# BaseCircuit.net
KiCad netlist of a schematic drawn in Altium Designer
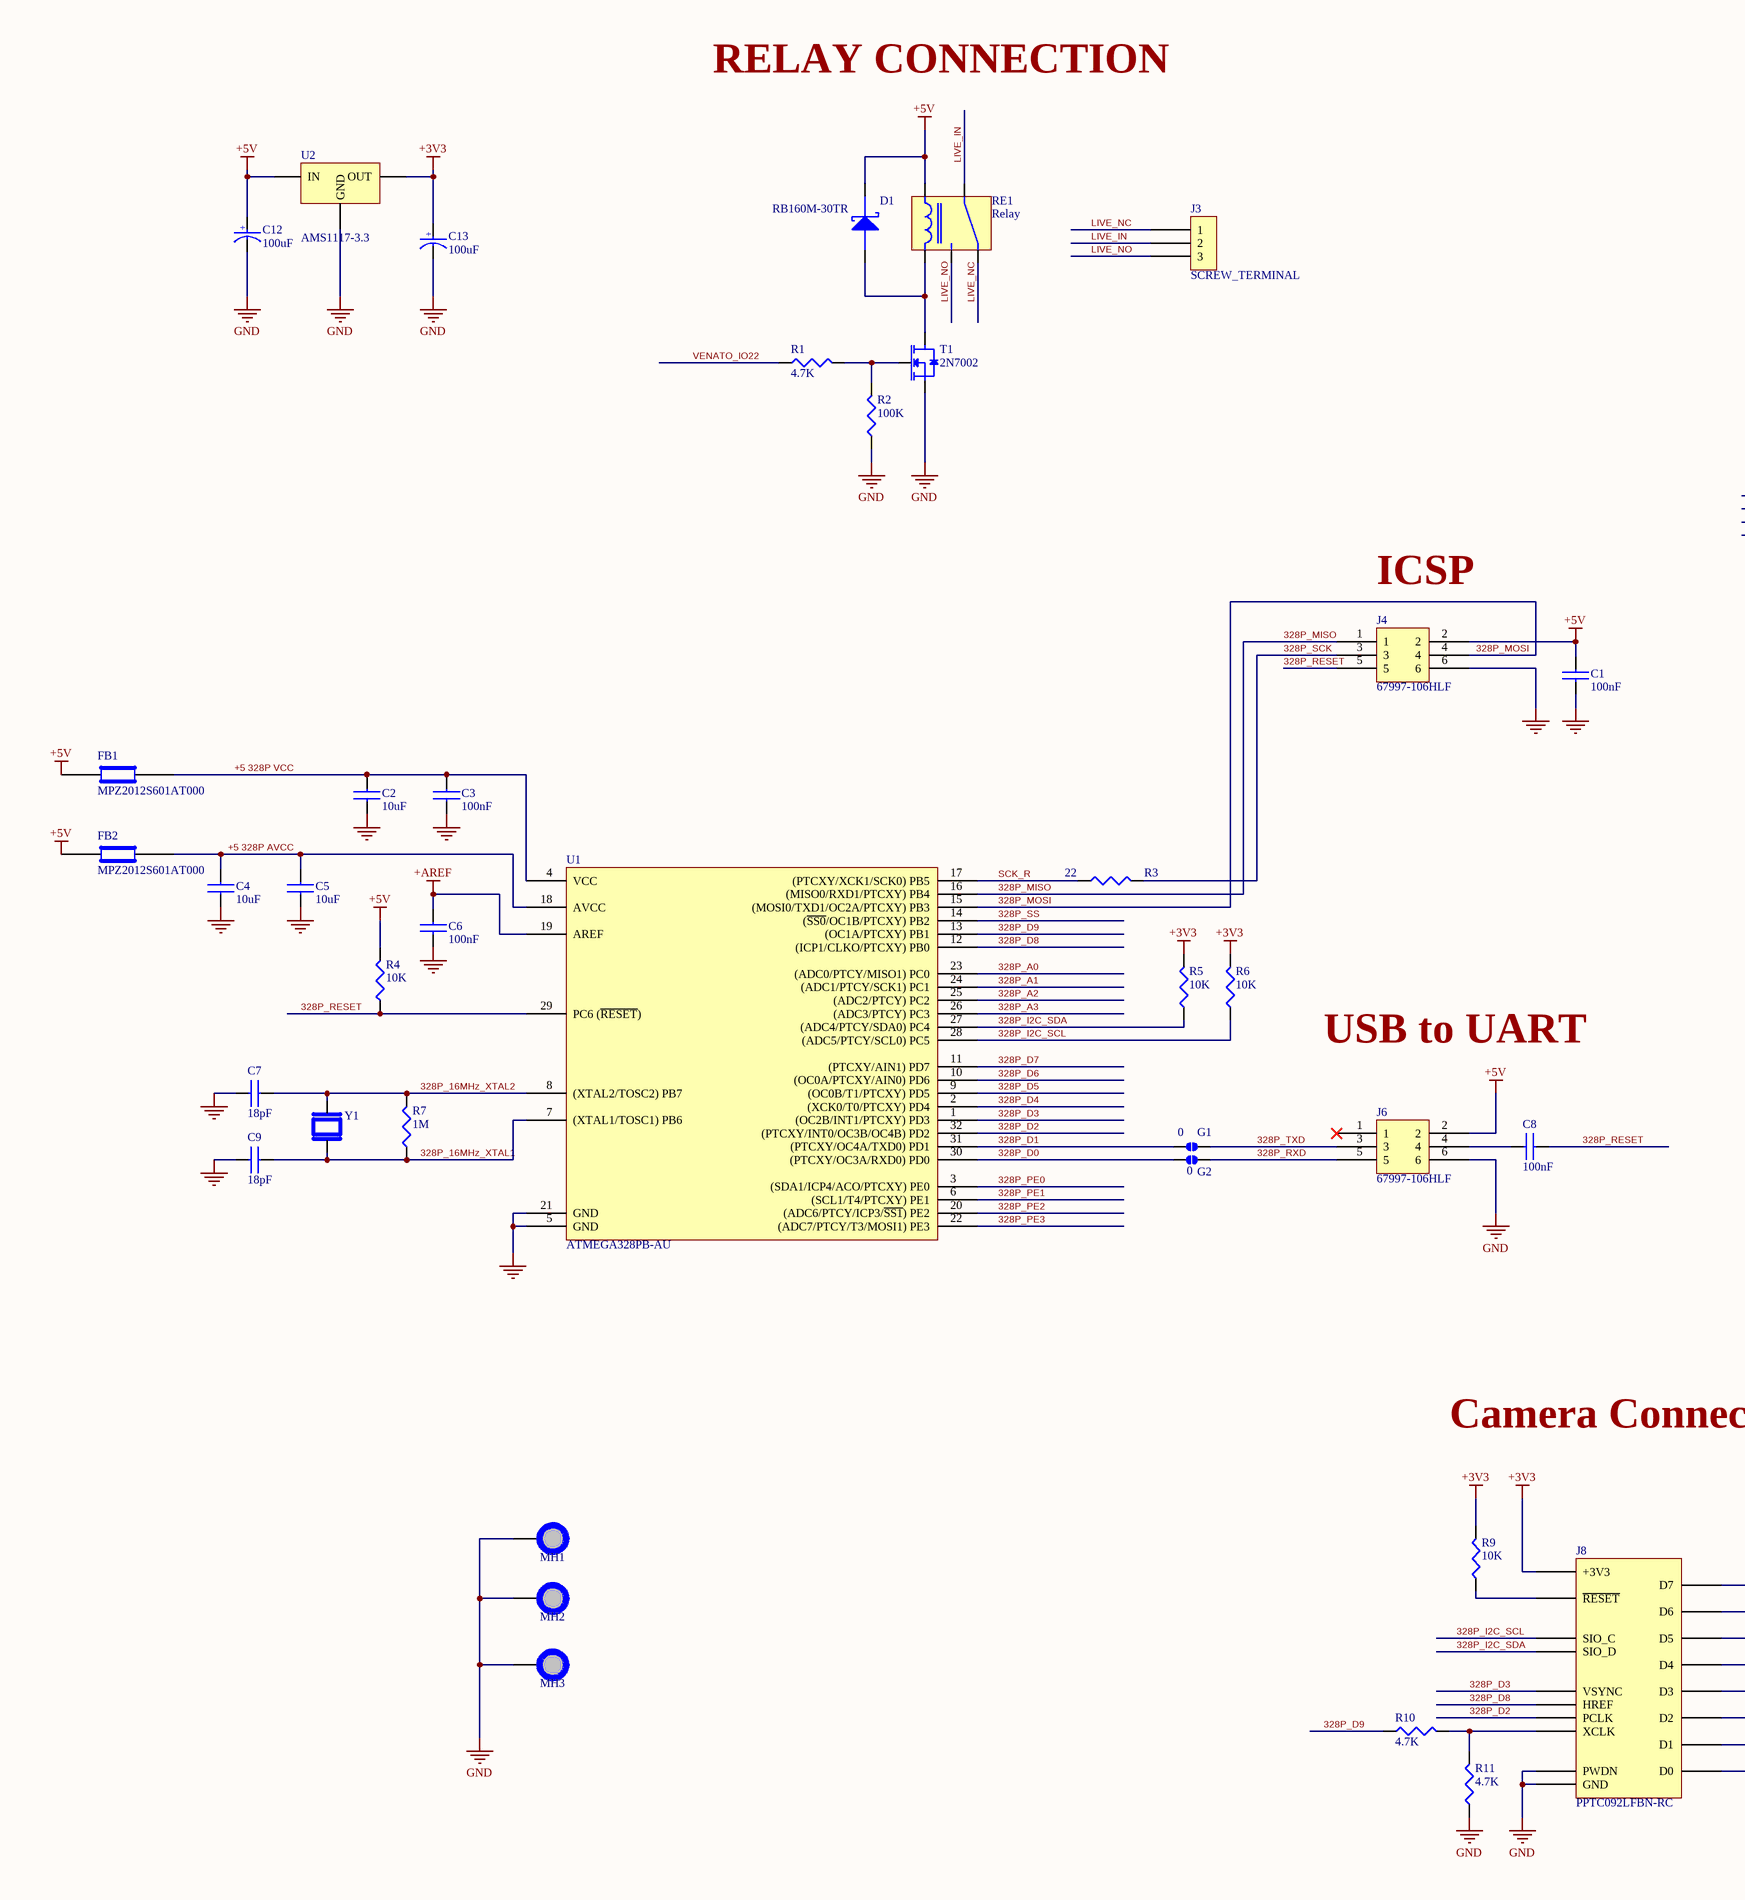
[diagram p0: BaseCircuit.SchDoc, left]
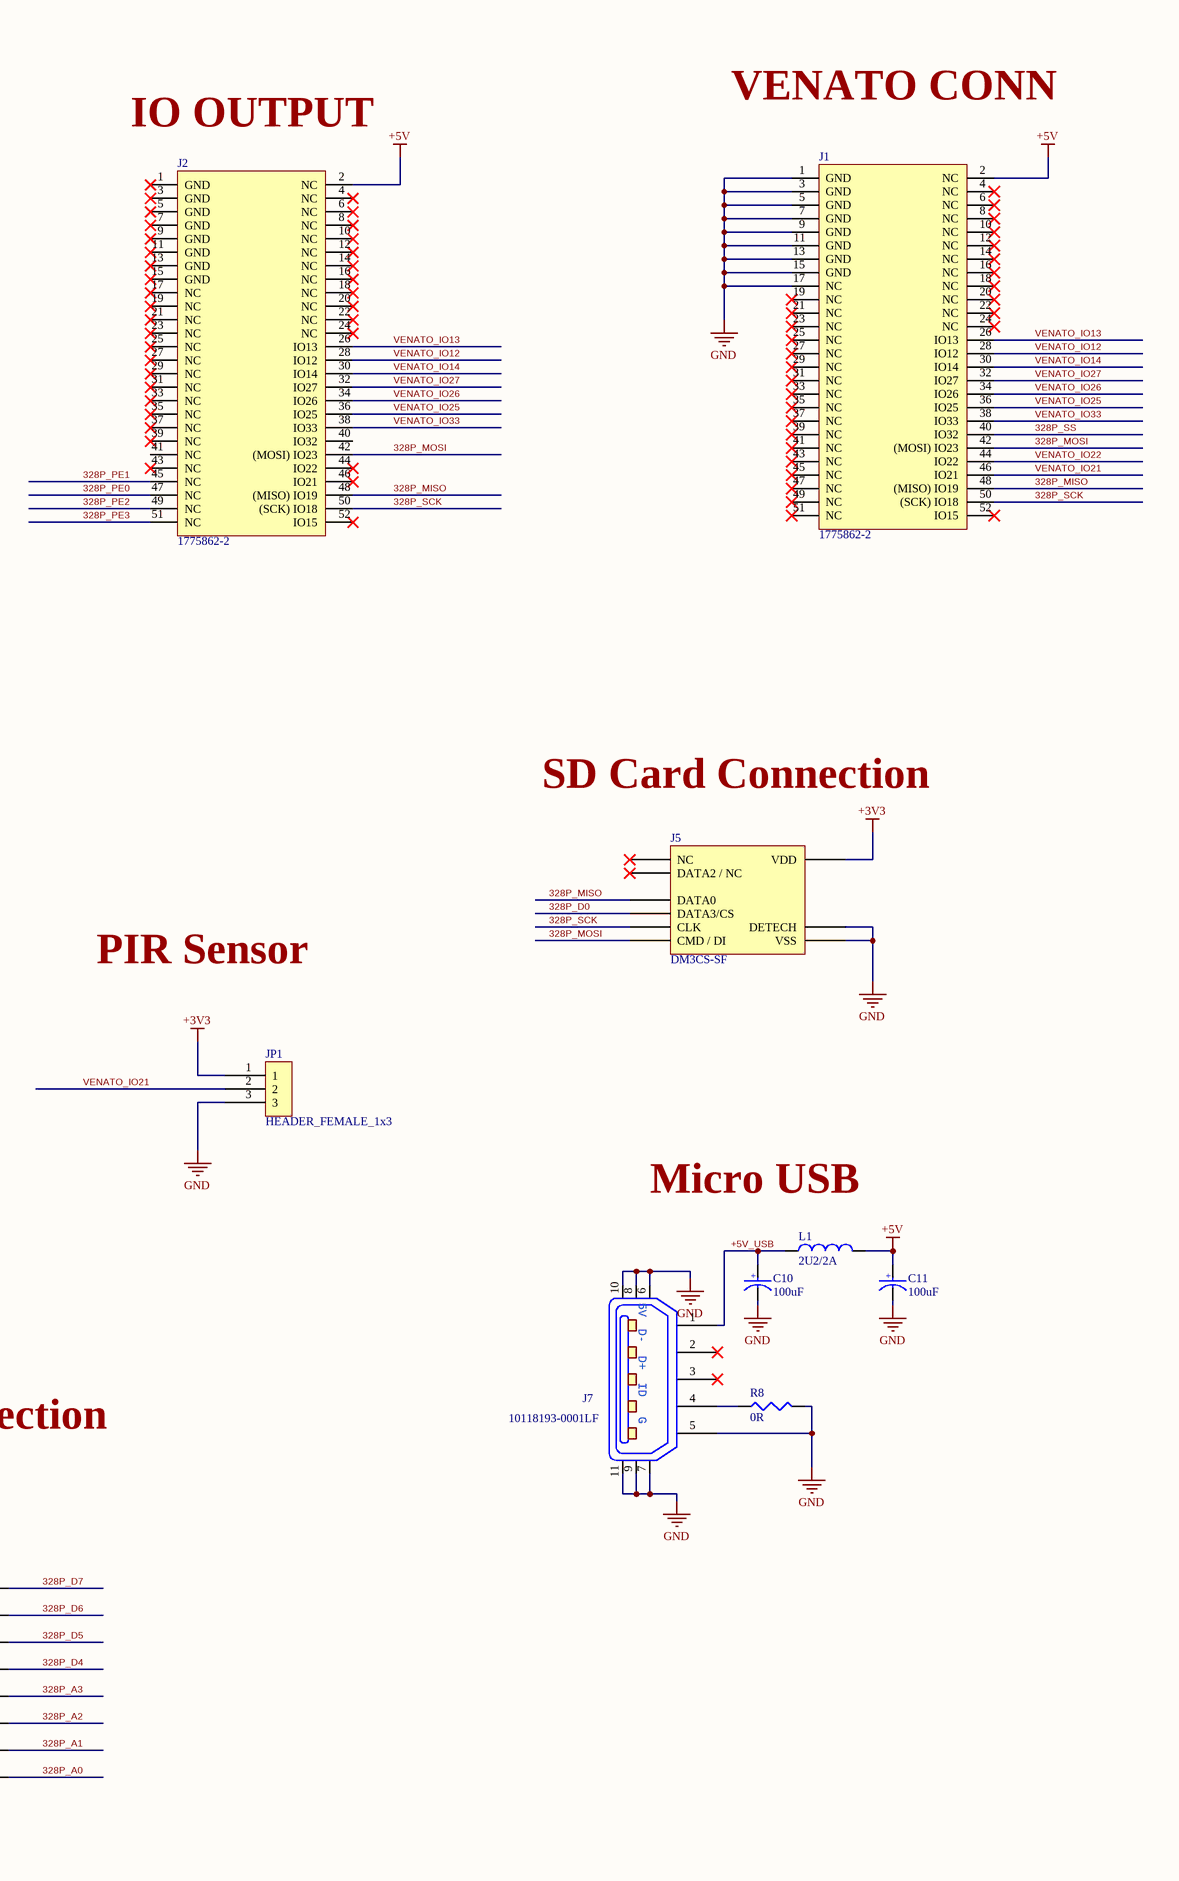
[diagram p1: BaseCircuit.SchDoc, right]

(export (version "E")
  (design (tool "Eeschema 10.0.6"))
  (components
    (comp (ref "C1")
      (value "100nF")
      (footprint "C0805")
      (description "Cap Ceramic 0.1uF 50V X7R 10% Pad SMD 0805 125°C Automotive T/R")
      (fields
        (field (name "MANUFACTURER") "TDK")
        (field (name "MANUFACTURER PART NUMBER") "CGA4J2X7R1H104K125AM")
      )
      (libsource (lib "atmega_shlib") (part "CGA4J2X7R1H104K125AM"))
    )
    (comp (ref "C2")
      (value "10uF")
      (footprint "C0805")
      (description "Cap Ceramic 10uF 10V X7S 20% Pad SMD 0805 125°C Low ESR Automotive T/R")
      (fields
        (field (name "MANUFACTURER") "TDK")
        (field (name "MANUFACTURER PART NUMBER") "CGA4J3X7S1A106M125AB")
      )
      (libsource (lib "atmega_shlib") (part "CGA4J3X7S1A106M125AB"))
    )
    (comp (ref "C3")
      (value "100nF")
      (footprint "C0805")
      (description "Cap Ceramic 0.1uF 50V X7R 10% Pad SMD 0805 125°C Automotive T/R")
      (fields
        (field (name "MANUFACTURER") "TDK")
        (field (name "MANUFACTURER PART NUMBER") "CGA4J2X7R1H104K125AM")
      )
      (libsource (lib "atmega_shlib") (part "CGA4J2X7R1H104K125AM"))
    )
    (comp (ref "C4")
      (value "10uF")
      (footprint "C0805")
      (description "Cap Ceramic 10uF 10V X7S 20% Pad SMD 0805 125°C Low ESR Automotive T/R")
      (fields
        (field (name "MANUFACTURER") "TDK")
        (field (name "MANUFACTURER PART NUMBER") "CGA4J3X7S1A106M125AB")
      )
      (libsource (lib "atmega_shlib") (part "CGA4J3X7S1A106M125AB"))
    )
    (comp (ref "C5")
      (value "10uF")
      (footprint "C0805")
      (description "Cap Ceramic 10uF 10V X7S 20% Pad SMD 0805 125°C Low ESR Automotive T/R")
      (fields
        (field (name "MANUFACTURER") "TDK")
        (field (name "MANUFACTURER PART NUMBER") "CGA4J3X7S1A106M125AB")
      )
      (libsource (lib "atmega_shlib") (part "CGA4J3X7S1A106M125AB"))
    )
    (comp (ref "C6")
      (value "100nF")
      (footprint "C0805")
      (description "Cap Ceramic 0.1uF 50V X7R 10% Pad SMD 0805 125°C Automotive T/R")
      (fields
        (field (name "MANUFACTURER") "TDK")
        (field (name "MANUFACTURER PART NUMBER") "CGA4J2X7R1H104K125AM")
      )
      (libsource (lib "atmega_shlib") (part "CGA4J2X7R1H104K125AM"))
    )
    (comp (ref "C7")
      (value "18pF")
      (footprint "C0805")
      (description "Cap Ceramic 18pF 50V C0G 5% SMD 0805 125C Paper T/R")
      (fields
        (field (name "MANUFACTURER") "KEMET")
        (field (name "MANUFACTURER PART NUMBER") "C0805C180J5GACTU")
      )
      (libsource (lib "atmega_shlib") (part "C0805C180J5GACTU"))
    )
    (comp (ref "C8")
      (value "100nF")
      (footprint "C0805")
      (description "Cap Ceramic 0.1uF 50V X7R 10% Pad SMD 0805 125°C Automotive T/R")
      (fields
        (field (name "MANUFACTURER") "TDK")
        (field (name "MANUFACTURER PART NUMBER") "CGA4J2X7R1H104K125AM")
      )
      (libsource (lib "atmega_shlib") (part "CGA4J2X7R1H104K125AM"))
    )
    (comp (ref "C9")
      (value "18pF")
      (footprint "C0805")
      (description "Cap Ceramic 18pF 50V C0G 5% SMD 0805 125C Paper T/R")
      (fields
        (field (name "MANUFACTURER") "KEMET")
        (field (name "MANUFACTURER PART NUMBER") "C0805C180J5GACTU")
      )
      (libsource (lib "atmega_shlib") (part "C0805C180J5GACTU"))
    )
    (comp (ref "C10")
      (value "100uF")
      (footprint "C_ALU_C_SIZE")
      (description "Cap Aluminum 100uF 10V 20% (5 X 5.4mm) SMD 50mA 1000 hr 85°C T/R")
      (fields
        (field (name "MANUFACTURER") "Panasonic")
        (field (name "MANUFACTURER PART NUMBER") "EEE-1AA101WR")
      )
      (libsource (lib "schmaticSMDv1") (part "EEE-1AA101WR"))
    )
    (comp (ref "C11")
      (value "100uF")
      (footprint "C_ALU_C_SIZE")
      (description "Cap Aluminum 100uF 10V 20% (5 X 5.4mm) SMD 50mA 1000 hr 85°C T/R")
      (fields
        (field (name "MANUFACTURER") "Panasonic")
        (field (name "MANUFACTURER PART NUMBER") "EEE-1AA101WR")
      )
      (libsource (lib "schmaticSMDv1") (part "EEE-1AA101WR"))
    )
    (comp (ref "C12")
      (value "100uF")
      (footprint "C_ALU_C_SIZE")
      (description "Cap Aluminum 100uF 10V 20% (5 X 5.4mm) SMD 50mA 1000 hr 85°C T/R")
      (fields
        (field (name "MANUFACTURER") "Panasonic")
        (field (name "MANUFACTURER PART NUMBER") "EEE-1AA101WR")
      )
      (libsource (lib "schmaticSMDv1") (part "EEE-1AA101WR"))
    )
    (comp (ref "C13")
      (value "100uF")
      (footprint "C_ALU_C_SIZE")
      (description "Cap Aluminum 100uF 10V 20% (5 X 5.4mm) SMD 50mA 1000 hr 85°C T/R")
      (fields
        (field (name "MANUFACTURER") "Panasonic")
        (field (name "MANUFACTURER PART NUMBER") "EEE-1AA101WR")
      )
      (libsource (lib "schmaticSMDv1") (part "EEE-1AA101WR"))
    )
    (comp (ref "D1")
      (value "RB160M-30TR")
      (footprint "SOD123")
      (description "DIODE SCHOTTKY 30V 1A PMDU")
      (fields (field (name "MANUFACTURER") "Rohm"))
      (libsource (lib "schmaticSMDv1") (part "RB160M-30TR"))
    )
    (comp (ref "FB1")
      (value "MPZ2012S601AT000")
      (footprint "C0805")
      (description "Ferrite Beads Multi-Layer Power 600Ohm 25% 100MHz 2A 100mOhm DCR 0805 T/R")
      (fields (field (name "MANUFACTURER") "TDK"))
      (libsource (lib "atmega_shlib") (part "MPZ2012S601AT000"))
    )
    (comp (ref "FB2")
      (value "MPZ2012S601AT000")
      (footprint "C0805")
      (description "Ferrite Beads Multi-Layer Power 600Ohm 25% 100MHz 2A 100mOhm DCR 0805 T/R")
      (fields (field (name "MANUFACTURER") "TDK"))
      (libsource (lib "atmega_shlib") (part "MPZ2012S601AT000"))
    )
    (comp (ref "G1")
      (value "0")
      (footprint "R0805_no_3d")
      (description "This is a gap that diconects line. you can connect it using soldier")
      (libsource (lib "schmaticSMDv1") (part "0Ohm gap"))
    )
    (comp (ref "G2")
      (value "0")
      (footprint "R0805_no_3d")
      (description "This is a gap that diconects line. you can connect it using soldier")
      (libsource (lib "schmaticSMDv1") (part "0Ohm gap"))
    )
    (comp (ref "J1")
      (value "1775862-2")
      (footprint "TE_1775862-2")
      (description "MSATA/MINI PCI-E 5.2H TYPE I G/F")
      (fields (field (name "MANUFACTURER") "TE Connectivity"))
      (libsource (lib "schmaticSMDv1") (part "1775862-2"))
    )
    (comp (ref "J2")
      (value "1775862-2")
      (footprint "TE_1775862-2")
      (description "MSATA/MINI PCI-E 5.2H TYPE I G/F")
      (fields (field (name "MANUFACTURER") "TE Connectivity"))
      (libsource (lib "schmaticSMDv1") (part "1775862-2"))
    )
    (comp (ref "J3")
      (value "SCREW_TERMINAL")
      (footprint "SCREW_TERMINAL_3_5.08MM")
      (libsource (lib "schmaticSMDv1") (part "SCREW_TERMINAL"))
    )
    (comp (ref "J4")
      (value "67997-106HLF")
      (footprint "HDR_2x3_2.54MM")
      (description "Conn Unshrouded Header HDR 6 POS 2.54mm Solder ST Top Entry Thru-Hole BergStik® Bulk")
      (fields (field (name "MANUFACTURER") "ICC"))
      (libsource (lib "atmega_shlib") (part "67997-106HLF"))
    )
    (comp (ref "J5")
      (value "DM3CS-SF")
      (footprint "GCT_MEM2051-00-195-00-A")
      (description "Connector, Memory, Micro Sd, Hinged Rohs Compliant: Yes")
      (fields (field (name "MANUFACTURER") "Hirose"))
      (libsource (lib "schmaticSMDv1") (part "DM3CS-SF"))
    )
    (comp (ref "J6")
      (value "67997-106HLF")
      (footprint "HDR_2x3_2.54MM")
      (description "Conn Unshrouded Header HDR 6 POS 2.54mm Solder ST Top Entry Thru-Hole BergStik® Bulk")
      (fields (field (name "MANUFACTURER") "ICC"))
      (libsource (lib "atmega_shlib") (part "67997-106HLF"))
    )
    (comp (ref "J7")
      (value "10118193-0001LF")
      (footprint "10118193-0001LF")
      (description "FCI Right Angle Surface Mount Mount Female USB Connector; 100 V ac; 1.8A")
      (fields (field (name "MANUFACTURER") "Amphenol ICC / FCI"))
      (libsource (lib "atmega_shlib") (part "10118193-0001LF"))
    )
    (comp (ref "J8")
      (value "PPTC092LFBN-RC")
      (footprint "HDR_2X9_2.54MM")
      (description "Connector Header 18 Position 0.100\" (2.54mm) Tin Through Hole")
      (fields (field (name "MANUFACTURER") "Sullins"))
      (libsource (lib "schmaticSMDv1") (part "PPTC092LFBN-RC"))
    )
    (comp (ref "JP1")
      (value "HEADER_FEMALE_1x3")
      (footprint "HDR_1x3_2.54MM")
      (description "Conn Unshrouded Header HDR 3 POS 2.54mm Solder ST Top Entry Thru-Hole BergStik® Automotive Bulk")
      (fields
        (field (name "MANUFACTURER") "Amphenol ICC")
        (field (name "MANUFACTURER PART NUMBER") "68000-103HLF")
      )
      (libsource (lib "atmega_shlib") (part "68000-103HLF"))
    )
    (comp (ref "L1")
      (value "2U2/2A")
      (footprint "CL_inductor")
      (description "Inductor RF Chip Wirewound 2.2uH 20% 100KHz 1.13A 0.104Ohm DCR 1210 T/R")
      (fields
        (field (name "MANUFACTURER") "KEMET")
        (field (name "MANUFACTURER PART NUMBER") "L1210R2R2MDWIT")
      )
      (libsource (lib "atmega_shlib") (part "L1210R2R2MDWIT"))
    )
    (comp (ref "MH1")
      (value "Mounting_hole_17.4_3.2")
      (footprint "MH_17.4_3.2")
      (description "Mounting Hole plated")
      (libsource (lib "schmaticSMDv1") (part "Mounting_hole_17.4_3.2"))
    )
    (comp (ref "MH2")
      (value "Mounting_hole_17.4_3.2")
      (footprint "MH_17.4_3.2")
      (description "Mounting Hole plated")
      (libsource (lib "schmaticSMDv1") (part "Mounting_hole_17.4_3.2"))
    )
    (comp (ref "MH3")
      (value "Mounting_hole_17.4_3.2")
      (footprint "MH_17.4_3.2")
      (description "Mounting Hole plated")
      (libsource (lib "schmaticSMDv1") (part "Mounting_hole_17.4_3.2"))
    )
    (comp (ref "R1")
      (value "4.7K")
      (footprint "R0805")
      (description "Res Thick Film 0805 4.7K Ohm 5% 0.125W(1/8W) ±100ppm/C Pad SMD T/R")
      (fields
        (field (name "MANUFACTURER") "Yageo")
        (field (name "MANUFACTURER PART NUMBER") "RC0805JR-074K7L")
      )
      (libsource (lib "schmaticSMDv1") (part "RC0805JR-074K7L"))
    )
    (comp (ref "R2")
      (value "100K")
      (footprint "R0805")
      (description "Res Thick Film 0805 100K Ohm 1% 1/8W ±100ppm/°C Molded SMD Paper T/R")
      (fields
        (field (name "MANUFACTURER") "Yageo")
        (field (name "MANUFACTURER PART NUMBER") "RC0805FR-07100KL")
      )
      (libsource (lib "schmaticSMDv1") (part "RC0805FR-07100KL"))
    )
    (comp (ref "R3")
      (value "22")
      (footprint "R0805")
      (description "Res SMD 0805 22R 1% 0.125W T.C.100PPM")
      (fields
        (field (name "MANUFACTURER") "Yageo")
        (field (name "MANUFACTURER PART NUMBER") "RC0805FR-0722RL")
      )
      (libsource (lib "atmega_shlib") (part "RC0805FR-0722RL"))
    )
    (comp (ref "R4")
      (value "10K")
      (footprint "R0805")
      (description "Res SMD 0805 10K 1% 0.125W T.C.100PPM")
      (fields
        (field (name "MANUFACTURER") "Yageo")
        (field (name "MANUFACTURER PART NUMBER") "RC0805FR-0710KL")
      )
      (libsource (lib "atmega_shlib") (part "RC0805FR-0710KL"))
    )
    (comp (ref "R5")
      (value "10K")
      (footprint "R0805")
      (description "Res SMD 0805 10K 1% 0.125W T.C.100PPM")
      (fields
        (field (name "MANUFACTURER") "Yageo")
        (field (name "MANUFACTURER PART NUMBER") "RC0805FR-0710KL")
      )
      (libsource (lib "schmaticSMDv1") (part "RC0805FR-0710KL"))
    )
    (comp (ref "R6")
      (value "10K")
      (footprint "R0805")
      (description "Res SMD 0805 10K 1% 0.125W T.C.100PPM")
      (fields
        (field (name "MANUFACTURER") "Yageo")
        (field (name "MANUFACTURER PART NUMBER") "RC0805FR-0710KL")
      )
      (libsource (lib "schmaticSMDv1") (part "RC0805FR-0710KL"))
    )
    (comp (ref "R7")
      (value "1M")
      (footprint "R0805")
      (description "Res Thick Film 0805 1M Ohm 1% 0.125W(1/8W) ±100ppm/C Pad SMD T/R")
      (fields
        (field (name "MANUFACTURER") "Yageo Phycomp")
        (field (name "MANUFACTURER PART NUMBER") "RC0805FR-071ML")
      )
      (libsource (lib "atmega_shlib") (part "RC0805FR-071ML"))
    )
    (comp (ref "R8")
      (value "0R")
      (footprint "R0805")
      (description "RC Series 0805 0.125 W 0 Ohm Jumper Surface Mount Thick Film Chip Resistor")
      (fields
        (field (name "MANUFACTURER") "Yageo")
        (field (name "MANUFACTURER PART NUMBER") "RC0805JR-070RL")
      )
      (libsource (lib "atmega_shlib") (part "RC0805JR-070RL"))
    )
    (comp (ref "R9")
      (value "10K")
      (footprint "R0805")
      (description "Res SMD 0805 10K 1% 0.125W T.C.100PPM")
      (fields
        (field (name "MANUFACTURER") "Yageo")
        (field (name "MANUFACTURER PART NUMBER") "RC0805FR-0710KL")
      )
      (libsource (lib "atmega_shlib") (part "RC0805FR-0710KL"))
    )
    (comp (ref "R10")
      (value "4.7K")
      (footprint "R0805")
      (description "Res Thick Film 0805 4.7K Ohm 5% 0.125W(1/8W) ±100ppm/C Pad SMD T/R")
      (fields
        (field (name "MANUFACTURER") "Yageo")
        (field (name "MANUFACTURER PART NUMBER") "RC0805JR-074K7L")
      )
      (libsource (lib "schmaticSMDv1") (part "RC0805JR-074K7L"))
    )
    (comp (ref "R11")
      (value "4.7K")
      (footprint "R0805")
      (description "Res Thick Film 0805 4.7K Ohm 5% 0.125W(1/8W) ±100ppm/C Pad SMD T/R")
      (fields
        (field (name "MANUFACTURER") "Yageo")
        (field (name "MANUFACTURER PART NUMBER") "RC0805JR-074K7L")
      )
      (libsource (lib "schmaticSMDv1") (part "RC0805JR-074K7L"))
    )
    (comp (ref "RE1")
      (value "Relay")
      (footprint "RELAY_5PIN")
      (libsource (lib "schmaticSMDv1") (part "Relay"))
    )
    (comp (ref "T1")
      (value "2N7002")
      (footprint "TRANS_MMBT2907A")
      (description "Transistor Mosfet N-ch 60V 0.3A 3-PIN SOT-23 T/r")
      (libsource (lib "schmaticSMDv1") (part "2N7002"))
    )
    (comp (ref "U1")
      (value "ATMEGA328PB-AU")
      (footprint "TQFP_32")
      (description "IC MCU 8BIT 32KB FLASH 32TQFP")
      (fields (field (name "MANUFACTURER") "Microchip"))
      (libsource (lib "schmaticSMDv1") (part "ATMEGA328PB-AU"))
    )
    (comp (ref "U2")
      (value "AMS1117-3.3")
      (footprint "SOT-223")
      (description "Fixed Positive LDO Regulator, 3.3V, 1.3V Dropout, PDSO3")
      (fields (field (name "MANUFACTURER") "Advanced Monolithic Systems"))
      (libsource (lib "schmaticSMDv1") (part "AMS1117-3.3"))
    )
    (comp (ref "Y1")
      (value "ABLS-16.000MHZ-B4-T")
      (footprint "XTAL_ABLS-16.000MHZ-B4-T")
      (description "Crystal 16MHz ±30ppm (Tol) ±50ppm (Stability) 18pF FUND 40Ohm 2-Pin HC-49/US SMD T/R")
      (fields (field (name "MANUFACTURER") "Abracon") (field (name "TOLERANCE") "30ppm"))
      (libsource (lib "schmaticSMDv1") (part "ABLS-16.000MHZ-B4-T"))
    )
  )
  (nets
    (net (code "1") (name "+3V3") (class "Default")
      (node (ref "C13") (pin "1") (pinfunction "1_1") (pintype "passive"))
      (node (ref "J5") (pin "4") (pinfunction "VDD_4") (pintype "passive"))
      (node (ref "J8") (pin "1") (pinfunction "+3V3_1") (pintype "passive"))
      (node (ref "JP1") (pin "1") (pinfunction "1_1") (pintype "passive"))
      (node (ref "R5") (pin "2") (pinfunction "2_2") (pintype "passive"))
      (node (ref "R6") (pin "2") (pinfunction "2_2") (pintype "passive"))
      (node (ref "R9") (pin "2") (pinfunction "2_2") (pintype "passive"))
      (node (ref "U2") (pin "2") (pinfunction "OUT_2") (pintype "passive"))
    )
    (net (code "2") (name "+5V") (class "Default")
      (node (ref "C1") (pin "2") (pinfunction "2_2") (pintype "passive"))
      (node (ref "C11") (pin "1") (pinfunction "1_1") (pintype "passive"))
      (node (ref "C12") (pin "1") (pinfunction "1_1") (pintype "passive"))
      (node (ref "D1") (pin "1") (pinfunction "Ca_1") (pintype "passive"))
      (node (ref "FB1") (pin "1") (pinfunction "1_1") (pintype "passive"))
      (node (ref "FB2") (pin "1") (pinfunction "1_1") (pintype "passive"))
      (node (ref "J1") (pin "2") (pinfunction "NC_2") (pintype "passive"))
      (node (ref "J2") (pin "2") (pinfunction "NC_2") (pintype "passive"))
      (node (ref "J4") (pin "2") (pinfunction "2_2") (pintype "passive"))
      (node (ref "J6") (pin "2") (pinfunction "2_2") (pintype "passive"))
      (node (ref "L1") (pin "2") (pinfunction "2_2") (pintype "passive"))
      (node (ref "R4") (pin "2") (pinfunction "2_2") (pintype "passive"))
      (node (ref "RE1") (pin "1") (pinfunction "1_1") (pintype "passive"))
      (node (ref "U2") (pin "3") (pinfunction "IN_3") (pintype "passive"))
    )
    (net (code "3") (name "+AREF") (class "Default")
      (node (ref "C6") (pin "2") (pinfunction "2_2") (pintype "passive"))
      (node (ref "U1") (pin "19") (pinfunction "AREF_19") (pintype "passive"))
    )
    (net (code "4") (name "/+5 328P AVCC") (class "Default")
      (node (ref "C4") (pin "2") (pinfunction "2_2") (pintype "passive"))
      (node (ref "C5") (pin "2") (pinfunction "2_2") (pintype "passive"))
      (node (ref "FB2") (pin "2") (pinfunction "2_2") (pintype "passive"))
      (node (ref "U1") (pin "18") (pinfunction "AVCC_18") (pintype "passive"))
    )
    (net (code "5") (name "/+5 328P VCC") (class "Default")
      (node (ref "C2") (pin "2") (pinfunction "2_2") (pintype "passive"))
      (node (ref "C3") (pin "2") (pinfunction "2_2") (pintype "passive"))
      (node (ref "FB1") (pin "2") (pinfunction "2_2") (pintype "passive"))
      (node (ref "U1") (pin "4") (pinfunction "VCC_4") (pintype "passive"))
    )
    (net (code "6") (name "/+5V_USB") (class "Default")
      (node (ref "C10") (pin "1") (pinfunction "1_1") (pintype "passive"))
      (node (ref "J7") (pin "1") (pinfunction "1_1") (pintype "passive"))
      (node (ref "L1") (pin "1") (pinfunction "1_1") (pintype "passive"))
    )
    (net (code "7") (name "/328P_16MHz_XTAL1") (class "Default")
      (node (ref "C9") (pin "2") (pinfunction "2_2") (pintype "passive"))
      (node (ref "R7") (pin "1") (pinfunction "1_1") (pintype "passive"))
      (node (ref "U1") (pin "7") (pinfunction "(XTAL1/TOSC1)_PB6_7") (pintype "passive"))
      (node (ref "Y1") (pin "1") (pinfunction "1_1") (pintype "passive"))
    )
    (net (code "8") (name "/328P_16MHz_XTAL2") (class "Default")
      (node (ref "C7") (pin "2") (pinfunction "2_2") (pintype "passive"))
      (node (ref "R7") (pin "2") (pinfunction "2_2") (pintype "passive"))
      (node (ref "U1") (pin "8") (pinfunction "(XTAL2/TOSC2)_PB7_8") (pintype "passive"))
      (node (ref "Y1") (pin "2") (pinfunction "2_2") (pintype "passive"))
    )
    (net (code "9") (name "/328P_A0") (class "Default")
      (node (ref "J8") (pin "16") (pinfunction "D0_16") (pintype "passive"))
      (node (ref "U1") (pin "23") (pinfunction "(ADC0/PTCY/MISO1)_PC0_23") (pintype "passive"))
    )
    (net (code "10") (name "/328P_A1") (class "Default")
      (node (ref "J8") (pin "15") (pinfunction "D1_15") (pintype "passive"))
      (node (ref "U1") (pin "24") (pinfunction "(ADC1/PTCY/SCK1)_PC1_24") (pintype "passive"))
    )
    (net (code "11") (name "/328P_A2") (class "Default")
      (node (ref "J8") (pin "14") (pinfunction "D2_14") (pintype "passive"))
      (node (ref "U1") (pin "25") (pinfunction "(ADC2/PTCY)_PC2_25") (pintype "passive"))
    )
    (net (code "12") (name "/328P_A3") (class "Default")
      (node (ref "J8") (pin "13") (pinfunction "D3_13") (pintype "passive"))
      (node (ref "U1") (pin "26") (pinfunction "(ADC3/PTCY)_PC3_26") (pintype "passive"))
    )
    (net (code "13") (name "/328P_D0") (class "Default")
      (node (ref "G2") (pin "2") (pinfunction "2_2") (pintype "passive"))
      (node (ref "J5") (pin "2") (pinfunction "DATA3/CS_2") (pintype "passive"))
      (node (ref "U1") (pin "30") (pinfunction "(PTCXY/OC3A/RXD0)_PD0_30") (pintype "passive"))
    )
    (net (code "14") (name "/328P_D1") (class "Default")
      (node (ref "G1") (pin "2") (pinfunction "2_2") (pintype "passive"))
      (node (ref "U1") (pin "31") (pinfunction "(PTCXY/OC4A/TXD0)_PD1_31") (pintype "passive"))
    )
    (net (code "15") (name "/328P_D2") (class "Default")
      (node (ref "J8") (pin "7") (pinfunction "PCLK_7") (pintype "passive"))
      (node (ref "U1") (pin "32") (pinfunction "(PTCXY/INT0/OC3B/OC4B)_PD2_32") (pintype "passive"))
    )
    (net (code "16") (name "/328P_D3") (class "Default")
      (node (ref "J8") (pin "5") (pinfunction "VSYNC_5") (pintype "passive"))
      (node (ref "U1") (pin "1") (pinfunction "(OC2B/INT1/PTCXY)_PD3_1") (pintype "passive"))
    )
    (net (code "17") (name "/328P_D4") (class "Default")
      (node (ref "J8") (pin "12") (pinfunction "D4_12") (pintype "passive"))
      (node (ref "U1") (pin "2") (pinfunction "(XCK0/T0/PTCXY)_PD4_2") (pintype "passive"))
    )
    (net (code "18") (name "/328P_D5") (class "Default")
      (node (ref "J8") (pin "11") (pinfunction "D5_11") (pintype "passive"))
      (node (ref "U1") (pin "9") (pinfunction "(OC0B/T1/PTCXY)_PD5_9") (pintype "passive"))
    )
    (net (code "19") (name "/328P_D6") (class "Default")
      (node (ref "J8") (pin "10") (pinfunction "D6_10") (pintype "passive"))
      (node (ref "U1") (pin "10") (pinfunction "(OC0A/PTCXY/AIN0)_PD6_10") (pintype "passive"))
    )
    (net (code "20") (name "/328P_D7") (class "Default")
      (node (ref "J8") (pin "9") (pinfunction "D7_9") (pintype "passive"))
      (node (ref "U1") (pin "11") (pinfunction "(PTCXY/AIN1)_PD7_11") (pintype "passive"))
    )
    (net (code "21") (name "/328P_D8") (class "Default")
      (node (ref "J8") (pin "6") (pinfunction "HREF_6") (pintype "passive"))
      (node (ref "U1") (pin "12") (pinfunction "(ICP1/CLKO/PTCXY)_PB0_12") (pintype "passive"))
    )
    (net (code "22") (name "/328P_D9") (class "Default")
      (node (ref "R10") (pin "1") (pinfunction "1_1") (pintype "passive"))
      (node (ref "U1") (pin "13") (pinfunction "(OC1A/PTCXY)_PB1_13") (pintype "passive"))
    )
    (net (code "23") (name "/328P_I2C_SCL") (class "Default")
      (node (ref "J8") (pin "3") (pinfunction "SIO_C_3") (pintype "passive"))
      (node (ref "R6") (pin "1") (pinfunction "1_1") (pintype "passive"))
      (node (ref "U1") (pin "28") (pinfunction "(ADC5/PTCY/SCL0)_PC5_28") (pintype "passive"))
    )
    (net (code "24") (name "/328P_I2C_SDA") (class "Default")
      (node (ref "J8") (pin "4") (pinfunction "SIO_D_4") (pintype "passive"))
      (node (ref "R5") (pin "1") (pinfunction "1_1") (pintype "passive"))
      (node (ref "U1") (pin "27") (pinfunction "(ADC4/PTCY/SDA0)_PC4_27") (pintype "passive"))
    )
    (net (code "25") (name "/328P_MISO") (class "Default")
      (node (ref "J1") (pin "48") (pinfunction "(MISO)_IO19_48") (pintype "passive"))
      (node (ref "J2") (pin "48") (pinfunction "(MISO)_IO19_48") (pintype "passive"))
      (node (ref "J4") (pin "1") (pinfunction "1_1") (pintype "passive"))
      (node (ref "J5") (pin "7") (pinfunction "DATA0_7") (pintype "passive"))
      (node (ref "U1") (pin "16") (pinfunction "(MISO0/RXD1/PTCXY)_PB4_16") (pintype "passive"))
    )
    (net (code "26") (name "/328P_MOSI") (class "Default")
      (node (ref "J1") (pin "42") (pinfunction "(MOSI)_IO23_42") (pintype "passive"))
      (node (ref "J2") (pin "42") (pinfunction "(MOSI)_IO23_42") (pintype "passive"))
      (node (ref "J4") (pin "4") (pinfunction "4_4") (pintype "passive"))
      (node (ref "J5") (pin "3") (pinfunction "CMD_/_DI_3") (pintype "passive"))
      (node (ref "U1") (pin "15") (pinfunction "(MOSI0/TXD1/OC2A/PTCXY)_PB3_15") (pintype "passive"))
    )
    (net (code "27") (name "/328P_PE0") (class "Default")
      (node (ref "J2") (pin "47") (pinfunction "NC_47") (pintype "passive"))
      (node (ref "U1") (pin "3") (pinfunction "(SDA1/ICP4/ACO/PTCXY)_PE0_3") (pintype "passive"))
    )
    (net (code "28") (name "/328P_PE1") (class "Default")
      (node (ref "J2") (pin "45") (pinfunction "NC_45") (pintype "passive"))
      (node (ref "U1") (pin "6") (pinfunction "(SCL1/T4/PTCXY)_PE1_6") (pintype "passive"))
    )
    (net (code "29") (name "/328P_PE2") (class "Default")
      (node (ref "J2") (pin "49") (pinfunction "NC_49") (pintype "passive"))
      (node (ref "U1") (pin "20") (pinfunction "(ADC6/PTCY/ICP3/~{SS1})_PE2_20") (pintype "passive"))
    )
    (net (code "30") (name "/328P_PE3") (class "Default")
      (node (ref "J2") (pin "51") (pinfunction "NC_51") (pintype "passive"))
      (node (ref "U1") (pin "22") (pinfunction "(ADC7/PTCY/T3/MOSI1)_PE3_22") (pintype "passive"))
    )
    (net (code "31") (name "/328P_RESET") (class "Default")
      (node (ref "C8") (pin "1") (pinfunction "1_1") (pintype "passive"))
      (node (ref "J4") (pin "5") (pinfunction "5_5") (pintype "passive"))
      (node (ref "R4") (pin "1") (pinfunction "1_1") (pintype "passive"))
      (node (ref "U1") (pin "29") (pinfunction "PC6_(~{RESET})_29") (pintype "passive"))
    )
    (net (code "32") (name "/328P_RXD") (class "Default")
      (node (ref "G2") (pin "1") (pinfunction "1_1") (pintype "passive"))
      (node (ref "J6") (pin "5") (pinfunction "5_5") (pintype "passive"))
    )
    (net (code "33") (name "/328P_SCK") (class "Default")
      (node (ref "J1") (pin "50") (pinfunction "(SCK)_IO18_50") (pintype "passive"))
      (node (ref "J2") (pin "50") (pinfunction "(SCK)_IO18_50") (pintype "passive"))
      (node (ref "J4") (pin "3") (pinfunction "3_3") (pintype "passive"))
      (node (ref "J5") (pin "5") (pinfunction "CLK_5") (pintype "passive"))
      (node (ref "R3") (pin "2") (pinfunction "2_2") (pintype "passive"))
    )
    (net (code "34") (name "/328P_SS") (class "Default")
      (node (ref "J1") (pin "40") (pinfunction "IO32_40") (pintype "passive"))
      (node (ref "U1") (pin "14") (pinfunction "(~{SS0}/OC1B/PTCXY)_PB2_14") (pintype "passive"))
    )
    (net (code "35") (name "/328P_TXD") (class "Default")
      (node (ref "G1") (pin "1") (pinfunction "1_1") (pintype "passive"))
      (node (ref "J6") (pin "3") (pinfunction "3_3") (pintype "passive"))
    )
    (net (code "36") (name "/LIVE_IN") (class "Default")
      (node (ref "J3") (pin "2") (pinfunction "2_2") (pintype "passive"))
      (node (ref "RE1") (pin "5") (pinfunction "5_5") (pintype "passive"))
    )
    (net (code "37") (name "/LIVE_NC") (class "Default")
      (node (ref "J3") (pin "1") (pinfunction "1_1") (pintype "passive"))
      (node (ref "RE1") (pin "3") (pinfunction "3_3") (pintype "passive"))
    )
    (net (code "38") (name "/LIVE_NO") (class "Default")
      (node (ref "J3") (pin "3") (pinfunction "3_3") (pintype "passive"))
      (node (ref "RE1") (pin "4") (pinfunction "4_4") (pintype "passive"))
    )
    (net (code "39") (name "/SCK_R") (class "Default")
      (node (ref "R3") (pin "1") (pinfunction "1_1") (pintype "passive"))
      (node (ref "U1") (pin "17") (pinfunction "(PTCXY/XCK1/SCK0)_PB5_17") (pintype "passive"))
    )
    (net (code "40") (name "/VENATO_IO12") (class "Default")
      (node (ref "J1") (pin "28") (pinfunction "IO12_28") (pintype "passive"))
      (node (ref "J2") (pin "28") (pinfunction "IO12_28") (pintype "passive"))
    )
    (net (code "41") (name "/VENATO_IO13") (class "Default")
      (node (ref "J1") (pin "26") (pinfunction "IO13_26") (pintype "passive"))
      (node (ref "J2") (pin "26") (pinfunction "IO13_26") (pintype "passive"))
    )
    (net (code "42") (name "/VENATO_IO14") (class "Default")
      (node (ref "J1") (pin "30") (pinfunction "IO14_30") (pintype "passive"))
      (node (ref "J2") (pin "30") (pinfunction "IO14_30") (pintype "passive"))
    )
    (net (code "43") (name "/VENATO_IO21") (class "Default")
      (node (ref "J1") (pin "46") (pinfunction "IO21_46") (pintype "passive"))
      (node (ref "JP1") (pin "2") (pinfunction "2_2") (pintype "passive"))
    )
    (net (code "44") (name "/VENATO_IO22") (class "Default")
      (node (ref "J1") (pin "44") (pinfunction "IO22_44") (pintype "passive"))
      (node (ref "R1") (pin "1") (pinfunction "1_1") (pintype "passive"))
    )
    (net (code "45") (name "/VENATO_IO25") (class "Default")
      (node (ref "J1") (pin "36") (pinfunction "IO25_36") (pintype "passive"))
      (node (ref "J2") (pin "36") (pinfunction "IO25_36") (pintype "passive"))
    )
    (net (code "46") (name "/VENATO_IO26") (class "Default")
      (node (ref "J1") (pin "34") (pinfunction "IO26_34") (pintype "passive"))
      (node (ref "J2") (pin "34") (pinfunction "IO26_34") (pintype "passive"))
    )
    (net (code "47") (name "/VENATO_IO27") (class "Default")
      (node (ref "J1") (pin "32") (pinfunction "IO27_32") (pintype "passive"))
      (node (ref "J2") (pin "32") (pinfunction "IO27_32") (pintype "passive"))
    )
    (net (code "48") (name "/VENATO_IO33") (class "Default")
      (node (ref "J1") (pin "38") (pinfunction "IO33_38") (pintype "passive"))
      (node (ref "J2") (pin "38") (pinfunction "IO33_38") (pintype "passive"))
    )
    (net (code "49") (name "GND") (class "Default")
      (node (ref "C1") (pin "1") (pinfunction "1_1") (pintype "passive"))
      (node (ref "C10") (pin "2") (pinfunction "2_2") (pintype "passive"))
      (node (ref "C11") (pin "2") (pinfunction "2_2") (pintype "passive"))
      (node (ref "C12") (pin "2") (pinfunction "2_2") (pintype "passive"))
      (node (ref "C13") (pin "2") (pinfunction "2_2") (pintype "passive"))
      (node (ref "C2") (pin "1") (pinfunction "1_1") (pintype "passive"))
      (node (ref "C3") (pin "1") (pinfunction "1_1") (pintype "passive"))
      (node (ref "C4") (pin "1") (pinfunction "1_1") (pintype "passive"))
      (node (ref "C5") (pin "1") (pinfunction "1_1") (pintype "passive"))
      (node (ref "C6") (pin "1") (pinfunction "1_1") (pintype "passive"))
      (node (ref "C7") (pin "1") (pinfunction "1_1") (pintype "passive"))
      (node (ref "C9") (pin "1") (pinfunction "1_1") (pintype "passive"))
      (node (ref "J1") (pin "1") (pinfunction "GND_1") (pintype "passive"))
      (node (ref "J1") (pin "11") (pinfunction "GND_11") (pintype "passive"))
      (node (ref "J1") (pin "13") (pinfunction "GND_13") (pintype "passive"))
      (node (ref "J1") (pin "15") (pinfunction "GND_15") (pintype "passive"))
      (node (ref "J1") (pin "17") (pinfunction "NC_17") (pintype "passive"))
      (node (ref "J1") (pin "3") (pinfunction "GND_3") (pintype "passive"))
      (node (ref "J1") (pin "5") (pinfunction "GND_5") (pintype "passive"))
      (node (ref "J1") (pin "7") (pinfunction "GND_7") (pintype "passive"))
      (node (ref "J1") (pin "9") (pinfunction "GND_9") (pintype "passive"))
      (node (ref "J4") (pin "6") (pinfunction "6_6") (pintype "passive"))
      (node (ref "J5") (pin "6") (pinfunction "VSS_6") (pintype "passive"))
      (node (ref "J5") (pin "9") (pinfunction "DETECH_9") (pintype "passive"))
      (node (ref "J6") (pin "6") (pinfunction "6_6") (pintype "passive"))
      (node (ref "J7") (pin "10") (pinfunction "10_10") (pintype "passive"))
      (node (ref "J7") (pin "11") (pinfunction "11_11") (pintype "passive"))
      (node (ref "J7") (pin "5") (pinfunction "5_5") (pintype "passive"))
      (node (ref "J7") (pin "6") (pinfunction "6_6") (pintype "passive"))
      (node (ref "J7") (pin "7") (pinfunction "7_7") (pintype "passive"))
      (node (ref "J7") (pin "8") (pinfunction "8_8") (pintype "passive"))
      (node (ref "J7") (pin "9") (pinfunction "9_9") (pintype "passive"))
      (node (ref "J8") (pin "18") (pinfunction "PWDN_18") (pintype "passive"))
      (node (ref "J8") (pin "2") (pinfunction "GND_2") (pintype "passive"))
      (node (ref "JP1") (pin "3") (pinfunction "3_3") (pintype "passive"))
      (node (ref "MH1") (pin "1") (pinfunction "1_1") (pintype "passive"))
      (node (ref "MH2") (pin "1") (pinfunction "1_1") (pintype "passive"))
      (node (ref "MH3") (pin "1") (pinfunction "1_1") (pintype "passive"))
      (node (ref "R11") (pin "1") (pinfunction "1_1") (pintype "passive"))
      (node (ref "R2") (pin "1") (pinfunction "1_1") (pintype "passive"))
      (node (ref "R8") (pin "2") (pinfunction "2_2") (pintype "passive"))
      (node (ref "T1") (pin "1") (pinfunction "1_1") (pintype "passive"))
      (node (ref "U1") (pin "21") (pinfunction "GND_21") (pintype "passive"))
      (node (ref "U1") (pin "5") (pinfunction "GND_5") (pintype "passive"))
      (node (ref "U2") (pin "1") (pinfunction "GND_1") (pintype "passive"))
    )
    (net (code "50") (name "Net-(C8-Pad2)") (class "Default")
      (node (ref "C8") (pin "2") (pinfunction "2_2") (pintype "passive"))
      (node (ref "J6") (pin "4") (pinfunction "4_4") (pintype "passive"))
    )
    (net (code "51") (name "Net-(D1-An)") (class "Default")
      (node (ref "D1") (pin "2") (pinfunction "An_2") (pintype "passive"))
      (node (ref "RE1") (pin "2") (pinfunction "2_2") (pintype "passive"))
      (node (ref "T1") (pin "2") (pinfunction "2_2") (pintype "passive"))
    )
    (net (code "52") (name "Net-(J7-Pad4)") (class "Default")
      (node (ref "J7") (pin "4") (pinfunction "4_4") (pintype "passive"))
      (node (ref "R8") (pin "1") (pinfunction "1_1") (pintype "passive"))
    )
    (net (code "53") (name "Net-(J8-XCLK)") (class "Default")
      (node (ref "J8") (pin "8") (pinfunction "XCLK_8") (pintype "passive"))
      (node (ref "R10") (pin "2") (pinfunction "2_2") (pintype "passive"))
      (node (ref "R11") (pin "2") (pinfunction "2_2") (pintype "passive"))
    )
    (net (code "54") (name "Net-(J8-~{RESET})") (class "Default")
      (node (ref "J8") (pin "17") (pinfunction "~{RESET}_17") (pintype "passive"))
      (node (ref "R9") (pin "1") (pinfunction "1_1") (pintype "passive"))
    )
    (net (code "55") (name "Net-(R1-Pad2)") (class "Default")
      (node (ref "R1") (pin "2") (pinfunction "2_2") (pintype "passive"))
      (node (ref "R2") (pin "2") (pinfunction "2_2") (pintype "passive"))
      (node (ref "T1") (pin "3") (pinfunction "3_3") (pintype "passive"))
    )
    (net (code "56") (name "unconnected-(J1-IO15-Pad52)") (class "Default")
      (node (ref "J1") (pin "52") (pinfunction "IO15_52") (pintype "passive+no_connect"))
    )
    (net (code "57") (name "unconnected-(J1-NC-Pad4)") (class "Default")
      (node (ref "J1") (pin "4") (pinfunction "NC_4") (pintype "passive+no_connect"))
    )
    (net (code "58") (name "unconnected-(J1-NC-Pad6)") (class "Default")
      (node (ref "J1") (pin "6") (pinfunction "NC_6") (pintype "passive+no_connect"))
    )
    (net (code "59") (name "unconnected-(J1-NC-Pad8)") (class "Default")
      (node (ref "J1") (pin "8") (pinfunction "NC_8") (pintype "passive+no_connect"))
    )
    (net (code "60") (name "unconnected-(J1-NC-Pad10)") (class "Default")
      (node (ref "J1") (pin "10") (pinfunction "NC_10") (pintype "passive+no_connect"))
    )
    (net (code "61") (name "unconnected-(J1-NC-Pad12)") (class "Default")
      (node (ref "J1") (pin "12") (pinfunction "NC_12") (pintype "passive+no_connect"))
    )
    (net (code "62") (name "unconnected-(J1-NC-Pad14)") (class "Default")
      (node (ref "J1") (pin "14") (pinfunction "NC_14") (pintype "passive+no_connect"))
    )
    (net (code "63") (name "unconnected-(J1-NC-Pad16)") (class "Default")
      (node (ref "J1") (pin "16") (pinfunction "NC_16") (pintype "passive+no_connect"))
    )
    (net (code "64") (name "unconnected-(J1-NC-Pad18)") (class "Default")
      (node (ref "J1") (pin "18") (pinfunction "NC_18") (pintype "passive+no_connect"))
    )
    (net (code "65") (name "unconnected-(J1-NC-Pad19)") (class "Default")
      (node (ref "J1") (pin "19") (pinfunction "NC_19") (pintype "passive+no_connect"))
    )
    (net (code "66") (name "unconnected-(J1-NC-Pad20)") (class "Default")
      (node (ref "J1") (pin "20") (pinfunction "NC_20") (pintype "passive+no_connect"))
    )
    (net (code "67") (name "unconnected-(J1-NC-Pad21)") (class "Default")
      (node (ref "J1") (pin "21") (pinfunction "NC_21") (pintype "passive+no_connect"))
    )
    (net (code "68") (name "unconnected-(J1-NC-Pad22)") (class "Default")
      (node (ref "J1") (pin "22") (pinfunction "NC_22") (pintype "passive+no_connect"))
    )
    (net (code "69") (name "unconnected-(J1-NC-Pad23)") (class "Default")
      (node (ref "J1") (pin "23") (pinfunction "NC_23") (pintype "passive+no_connect"))
    )
    (net (code "70") (name "unconnected-(J1-NC-Pad24)") (class "Default")
      (node (ref "J1") (pin "24") (pinfunction "NC_24") (pintype "passive+no_connect"))
    )
    (net (code "71") (name "unconnected-(J1-NC-Pad25)") (class "Default")
      (node (ref "J1") (pin "25") (pinfunction "NC_25") (pintype "passive+no_connect"))
    )
    (net (code "72") (name "unconnected-(J1-NC-Pad27)") (class "Default")
      (node (ref "J1") (pin "27") (pinfunction "NC_27") (pintype "passive+no_connect"))
    )
    (net (code "73") (name "unconnected-(J1-NC-Pad29)") (class "Default")
      (node (ref "J1") (pin "29") (pinfunction "NC_29") (pintype "passive+no_connect"))
    )
    (net (code "74") (name "unconnected-(J1-NC-Pad31)") (class "Default")
      (node (ref "J1") (pin "31") (pinfunction "NC_31") (pintype "passive+no_connect"))
    )
    (net (code "75") (name "unconnected-(J1-NC-Pad33)") (class "Default")
      (node (ref "J1") (pin "33") (pinfunction "NC_33") (pintype "passive+no_connect"))
    )
    (net (code "76") (name "unconnected-(J1-NC-Pad35)") (class "Default")
      (node (ref "J1") (pin "35") (pinfunction "NC_35") (pintype "passive+no_connect"))
    )
    (net (code "77") (name "unconnected-(J1-NC-Pad37)") (class "Default")
      (node (ref "J1") (pin "37") (pinfunction "NC_37") (pintype "passive+no_connect"))
    )
    (net (code "78") (name "unconnected-(J1-NC-Pad39)") (class "Default")
      (node (ref "J1") (pin "39") (pinfunction "NC_39") (pintype "passive+no_connect"))
    )
    (net (code "79") (name "unconnected-(J1-NC-Pad41)") (class "Default")
      (node (ref "J1") (pin "41") (pinfunction "NC_41") (pintype "passive+no_connect"))
    )
    (net (code "80") (name "unconnected-(J1-NC-Pad43)") (class "Default")
      (node (ref "J1") (pin "43") (pinfunction "NC_43") (pintype "passive+no_connect"))
    )
    (net (code "81") (name "unconnected-(J1-NC-Pad45)") (class "Default")
      (node (ref "J1") (pin "45") (pinfunction "NC_45") (pintype "passive+no_connect"))
    )
    (net (code "82") (name "unconnected-(J1-NC-Pad47)") (class "Default")
      (node (ref "J1") (pin "47") (pinfunction "NC_47") (pintype "passive+no_connect"))
    )
    (net (code "83") (name "unconnected-(J1-NC-Pad49)") (class "Default")
      (node (ref "J1") (pin "49") (pinfunction "NC_49") (pintype "passive+no_connect"))
    )
    (net (code "84") (name "unconnected-(J1-NC-Pad51)") (class "Default")
      (node (ref "J1") (pin "51") (pinfunction "NC_51") (pintype "passive+no_connect"))
    )
    (net (code "85") (name "unconnected-(J2-GND-Pad1)") (class "Default")
      (node (ref "J2") (pin "1") (pinfunction "GND_1") (pintype "passive+no_connect"))
    )
    (net (code "86") (name "unconnected-(J2-GND-Pad3)") (class "Default")
      (node (ref "J2") (pin "3") (pinfunction "GND_3") (pintype "passive+no_connect"))
    )
    (net (code "87") (name "unconnected-(J2-GND-Pad5)") (class "Default")
      (node (ref "J2") (pin "5") (pinfunction "GND_5") (pintype "passive+no_connect"))
    )
    (net (code "88") (name "unconnected-(J2-GND-Pad7)") (class "Default")
      (node (ref "J2") (pin "7") (pinfunction "GND_7") (pintype "passive+no_connect"))
    )
    (net (code "89") (name "unconnected-(J2-GND-Pad9)") (class "Default")
      (node (ref "J2") (pin "9") (pinfunction "GND_9") (pintype "passive+no_connect"))
    )
    (net (code "90") (name "unconnected-(J2-GND-Pad11)") (class "Default")
      (node (ref "J2") (pin "11") (pinfunction "GND_11") (pintype "passive+no_connect"))
    )
    (net (code "91") (name "unconnected-(J2-GND-Pad13)") (class "Default")
      (node (ref "J2") (pin "13") (pinfunction "GND_13") (pintype "passive+no_connect"))
    )
    (net (code "92") (name "unconnected-(J2-GND-Pad15)") (class "Default")
      (node (ref "J2") (pin "15") (pinfunction "GND_15") (pintype "passive+no_connect"))
    )
    (net (code "93") (name "unconnected-(J2-IO15-Pad52)") (class "Default")
      (node (ref "J2") (pin "52") (pinfunction "IO15_52") (pintype "passive+no_connect"))
    )
    (net (code "94") (name "unconnected-(J2-IO21-Pad46)") (class "Default")
      (node (ref "J2") (pin "46") (pinfunction "IO21_46") (pintype "passive+no_connect"))
    )
    (net (code "95") (name "unconnected-(J2-IO22-Pad44)") (class "Default")
      (node (ref "J2") (pin "44") (pinfunction "IO22_44") (pintype "passive+no_connect"))
    )
    (net (code "96") (name "unconnected-(J2-IO32-Pad40)") (class "Default")
      (node (ref "J2") (pin "40") (pinfunction "IO32_40") (pintype "passive"))
    )
    (net (code "97") (name "unconnected-(J2-NC-Pad4)") (class "Default")
      (node (ref "J2") (pin "4") (pinfunction "NC_4") (pintype "passive+no_connect"))
    )
    (net (code "98") (name "unconnected-(J2-NC-Pad6)") (class "Default")
      (node (ref "J2") (pin "6") (pinfunction "NC_6") (pintype "passive+no_connect"))
    )
    (net (code "99") (name "unconnected-(J2-NC-Pad8)") (class "Default")
      (node (ref "J2") (pin "8") (pinfunction "NC_8") (pintype "passive+no_connect"))
    )
    (net (code "100") (name "unconnected-(J2-NC-Pad10)") (class "Default")
      (node (ref "J2") (pin "10") (pinfunction "NC_10") (pintype "passive+no_connect"))
    )
    (net (code "101") (name "unconnected-(J2-NC-Pad12)") (class "Default")
      (node (ref "J2") (pin "12") (pinfunction "NC_12") (pintype "passive+no_connect"))
    )
    (net (code "102") (name "unconnected-(J2-NC-Pad14)") (class "Default")
      (node (ref "J2") (pin "14") (pinfunction "NC_14") (pintype "passive+no_connect"))
    )
    (net (code "103") (name "unconnected-(J2-NC-Pad16)") (class "Default")
      (node (ref "J2") (pin "16") (pinfunction "NC_16") (pintype "passive+no_connect"))
    )
    (net (code "104") (name "unconnected-(J2-NC-Pad17)") (class "Default")
      (node (ref "J2") (pin "17") (pinfunction "NC_17") (pintype "passive+no_connect"))
    )
    (net (code "105") (name "unconnected-(J2-NC-Pad18)") (class "Default")
      (node (ref "J2") (pin "18") (pinfunction "NC_18") (pintype "passive+no_connect"))
    )
    (net (code "106") (name "unconnected-(J2-NC-Pad19)") (class "Default")
      (node (ref "J2") (pin "19") (pinfunction "NC_19") (pintype "passive+no_connect"))
    )
    (net (code "107") (name "unconnected-(J2-NC-Pad20)") (class "Default")
      (node (ref "J2") (pin "20") (pinfunction "NC_20") (pintype "passive+no_connect"))
    )
    (net (code "108") (name "unconnected-(J2-NC-Pad21)") (class "Default")
      (node (ref "J2") (pin "21") (pinfunction "NC_21") (pintype "passive+no_connect"))
    )
    (net (code "109") (name "unconnected-(J2-NC-Pad22)") (class "Default")
      (node (ref "J2") (pin "22") (pinfunction "NC_22") (pintype "passive+no_connect"))
    )
    (net (code "110") (name "unconnected-(J2-NC-Pad23)") (class "Default")
      (node (ref "J2") (pin "23") (pinfunction "NC_23") (pintype "passive+no_connect"))
    )
    (net (code "111") (name "unconnected-(J2-NC-Pad24)") (class "Default")
      (node (ref "J2") (pin "24") (pinfunction "NC_24") (pintype "passive+no_connect"))
    )
    (net (code "112") (name "unconnected-(J2-NC-Pad25)") (class "Default")
      (node (ref "J2") (pin "25") (pinfunction "NC_25") (pintype "passive+no_connect"))
    )
    (net (code "113") (name "unconnected-(J2-NC-Pad27)") (class "Default")
      (node (ref "J2") (pin "27") (pinfunction "NC_27") (pintype "passive+no_connect"))
    )
    (net (code "114") (name "unconnected-(J2-NC-Pad29)") (class "Default")
      (node (ref "J2") (pin "29") (pinfunction "NC_29") (pintype "passive+no_connect"))
    )
    (net (code "115") (name "unconnected-(J2-NC-Pad31)") (class "Default")
      (node (ref "J2") (pin "31") (pinfunction "NC_31") (pintype "passive+no_connect"))
    )
    (net (code "116") (name "unconnected-(J2-NC-Pad33)") (class "Default")
      (node (ref "J2") (pin "33") (pinfunction "NC_33") (pintype "passive+no_connect"))
    )
    (net (code "117") (name "unconnected-(J2-NC-Pad35)") (class "Default")
      (node (ref "J2") (pin "35") (pinfunction "NC_35") (pintype "passive+no_connect"))
    )
    (net (code "118") (name "unconnected-(J2-NC-Pad37)") (class "Default")
      (node (ref "J2") (pin "37") (pinfunction "NC_37") (pintype "passive+no_connect"))
    )
    (net (code "119") (name "unconnected-(J2-NC-Pad39)") (class "Default")
      (node (ref "J2") (pin "39") (pinfunction "NC_39") (pintype "passive+no_connect"))
    )
    (net (code "120") (name "unconnected-(J2-NC-Pad41)") (class "Default")
      (node (ref "J2") (pin "41") (pinfunction "NC_41") (pintype "passive"))
    )
    (net (code "121") (name "unconnected-(J2-NC-Pad43)") (class "Default")
      (node (ref "J2") (pin "43") (pinfunction "NC_43") (pintype "passive+no_connect"))
    )
    (net (code "122") (name "unconnected-(J5-DATA2_{slash}_NC-Pad1)") (class "Default")
      (node (ref "J5") (pin "1") (pinfunction "DATA2_/_NC_1") (pintype "passive+no_connect"))
    )
    (net (code "123") (name "unconnected-(J5-NC-Pad8)") (class "Default")
      (node (ref "J5") (pin "8") (pinfunction "NC_8") (pintype "passive+no_connect"))
    )
    (net (code "124") (name "unconnected-(J6-Pad1)") (class "Default")
      (node (ref "J6") (pin "1") (pinfunction "1_1") (pintype "passive+no_connect"))
    )
    (net (code "125") (name "unconnected-(J7-Pad2)") (class "Default")
      (node (ref "J7") (pin "2") (pinfunction "2_2") (pintype "passive+no_connect"))
    )
    (net (code "126") (name "unconnected-(J7-Pad3)") (class "Default")
      (node (ref "J7") (pin "3") (pinfunction "3_3") (pintype "passive+no_connect"))
    )
  )
)
